# PicoMiteVGAUSBV1_1.net
KiCad netlist of a schematic drawn in EasyEDA Pro
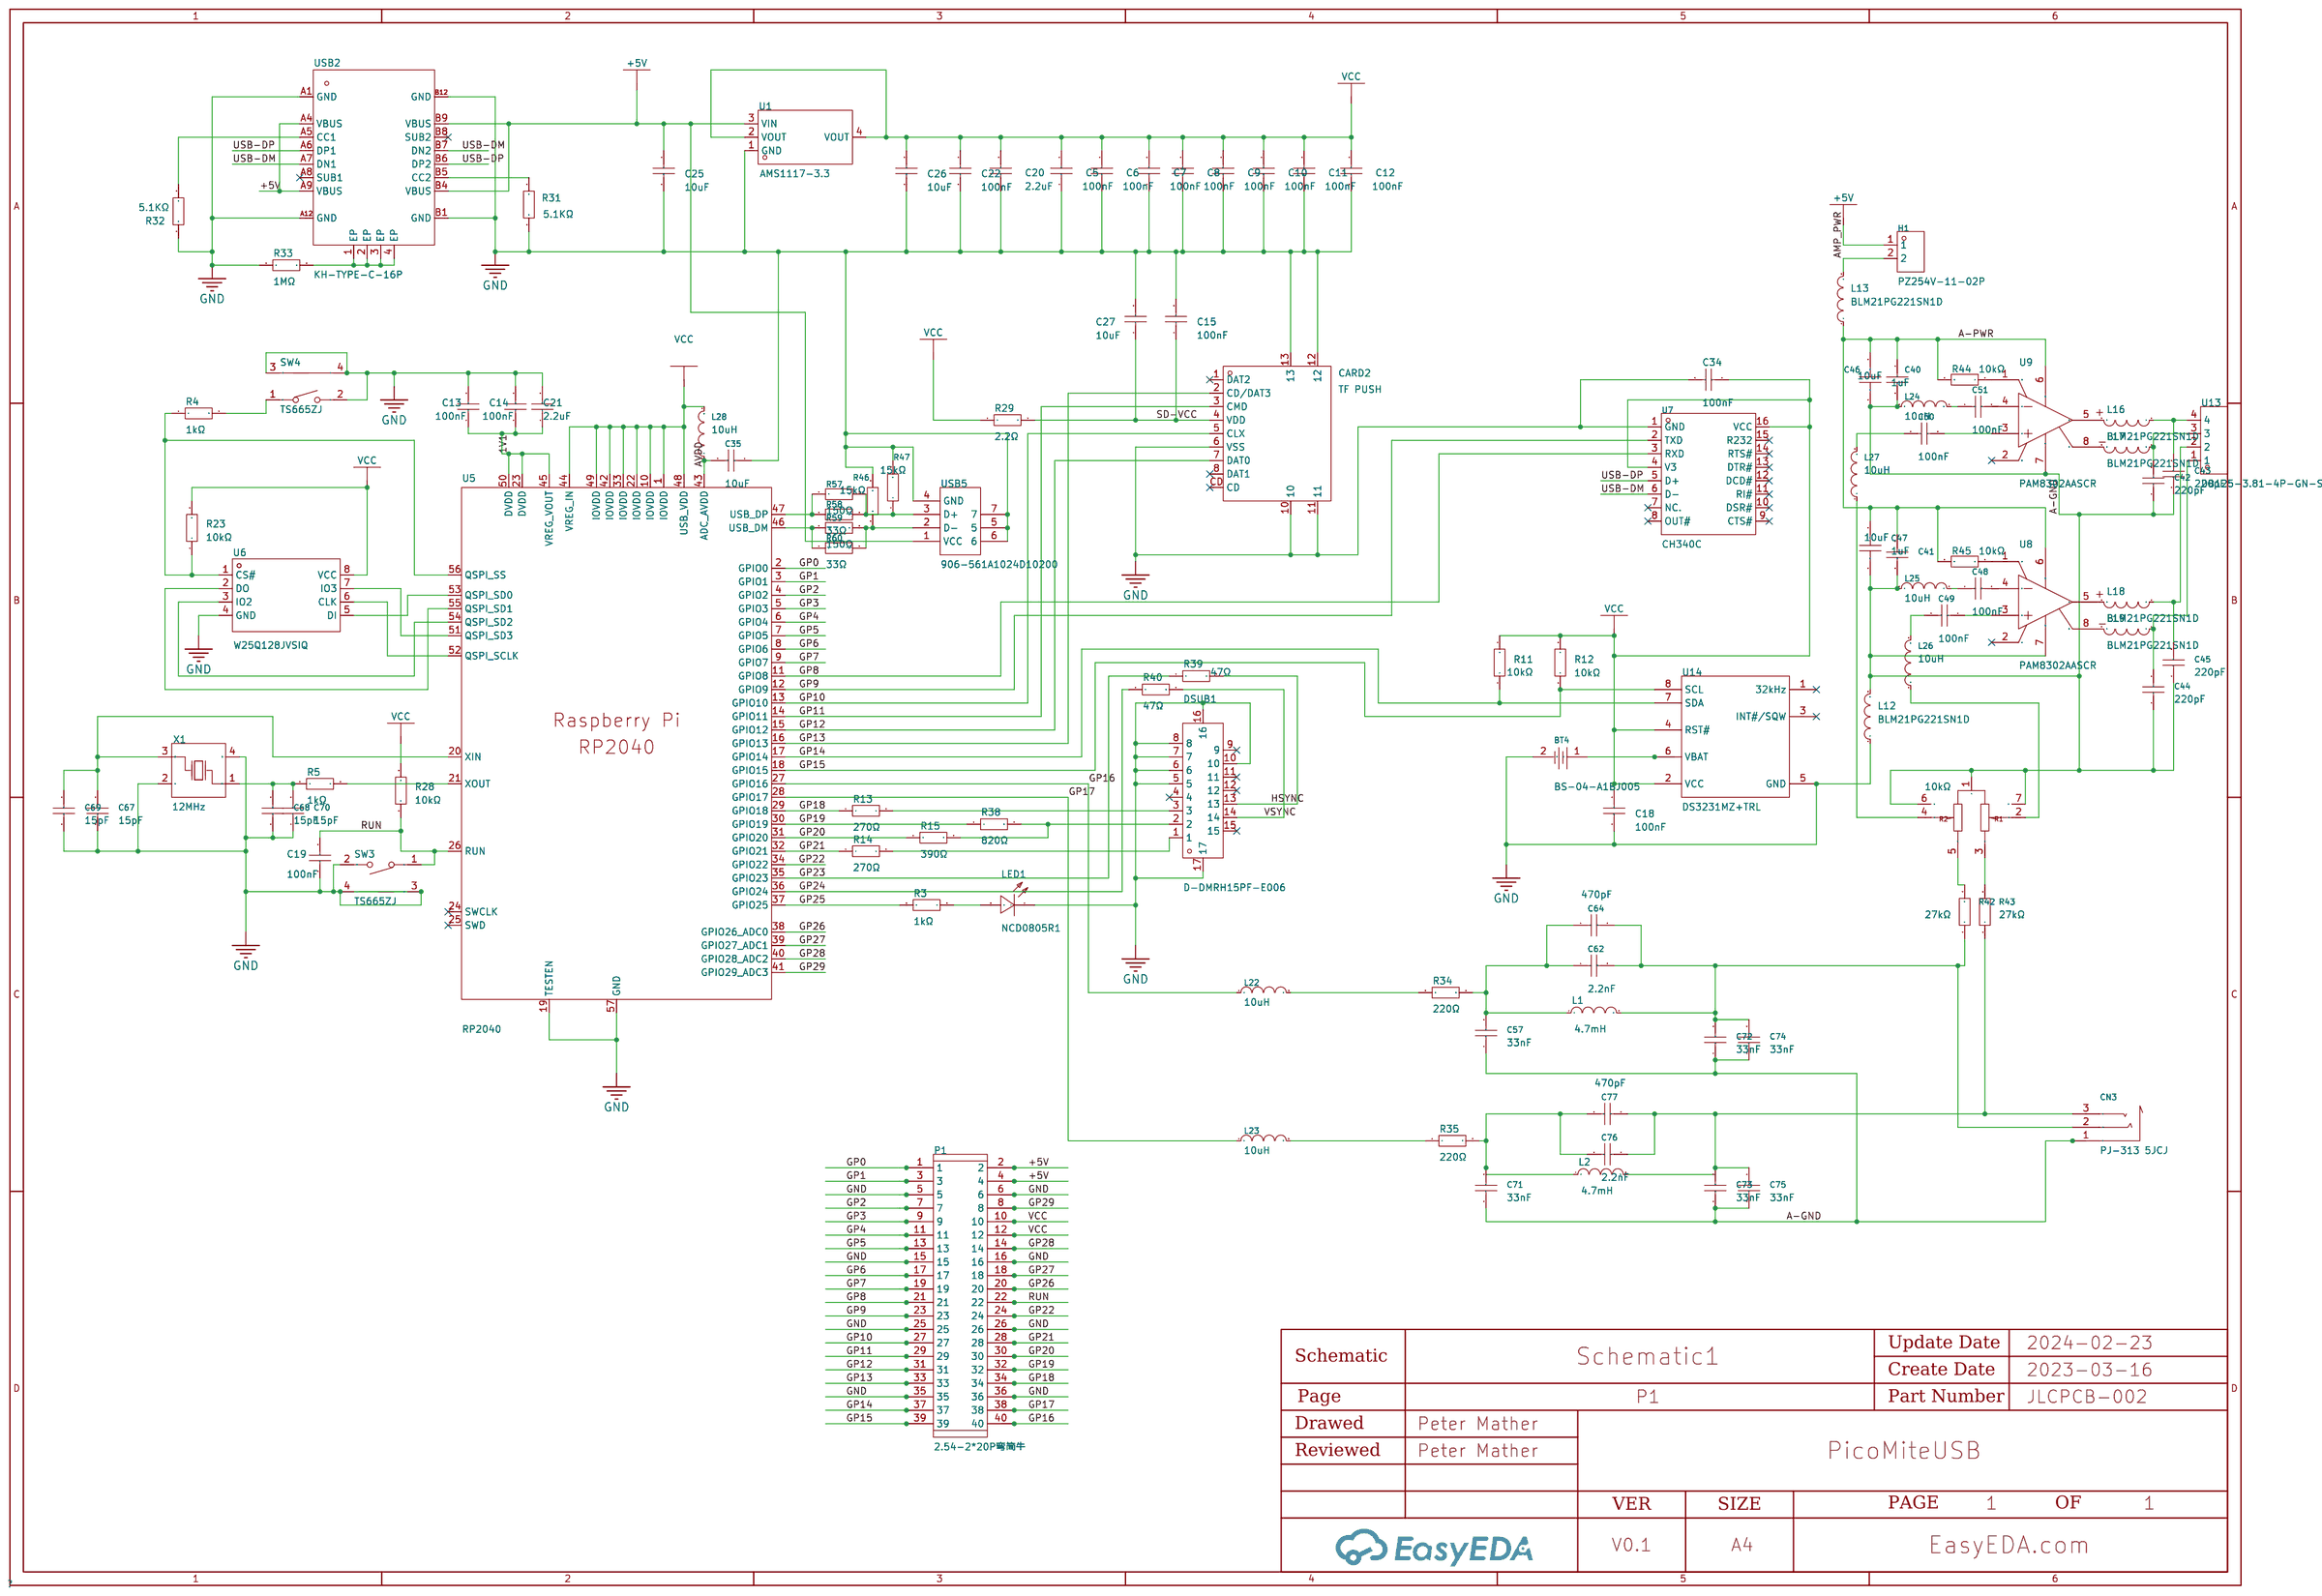
[diagram p0: schematic sheet]

(export (version "E")
  (design (tool "Eeschema 10.0.6"))
  (components
    (comp (ref "BT4")
      (value "BS-04-A1BJ005")
      (footprint "easyedapro:BAT-TH_BS-04-A1BJ004")
      (fields (field (name "Manufacturer") "MYOUNG(美阳)"))
      (libsource (lib "easyedapro") (part "BS-04-A1BJ005"))
    )
    (comp (ref "C5")
      (value "100nF")
      (footprint "easyedapro:C0603")
      (fields
        (field (name "Manufacturer Part") "CL05B104KO5NNNC")
        (field (name "Manufacturer") "SAMSUNG(三星)")
      )
      (libsource (lib "easyedapro") (part "CL10A225KO8NNNC"))
    )
    (comp (ref "C6")
      (value "100nF")
      (footprint "easyedapro:C0603")
      (fields
        (field (name "Manufacturer Part") "CL05B104KO5NNNC")
        (field (name "Manufacturer") "SAMSUNG(三星)")
      )
      (libsource (lib "easyedapro") (part "CL10A225KO8NNNC"))
    )
    (comp (ref "C7")
      (value "100nF")
      (footprint "easyedapro:C0603")
      (fields
        (field (name "Manufacturer Part") "CL05B104KO5NNNC")
        (field (name "Manufacturer") "SAMSUNG(三星)")
      )
      (libsource (lib "easyedapro") (part "CL10A225KO8NNNC"))
    )
    (comp (ref "C8")
      (value "100nF")
      (footprint "easyedapro:C0603")
      (fields
        (field (name "Manufacturer Part") "CL05B104KO5NNNC")
        (field (name "Manufacturer") "SAMSUNG(三星)")
      )
      (libsource (lib "easyedapro") (part "CL10A225KO8NNNC"))
    )
    (comp (ref "C9")
      (value "100nF")
      (footprint "easyedapro:C0603")
      (fields
        (field (name "Manufacturer Part") "CL05B104KO5NNNC")
        (field (name "Manufacturer") "SAMSUNG(三星)")
      )
      (libsource (lib "easyedapro") (part "CL10A225KO8NNNC"))
    )
    (comp (ref "C10")
      (value "100nF")
      (footprint "easyedapro:C0603")
      (fields
        (field (name "Manufacturer Part") "CL05B104KO5NNNC")
        (field (name "Manufacturer") "SAMSUNG(三星)")
      )
      (libsource (lib "easyedapro") (part "CL10A225KO8NNNC"))
    )
    (comp (ref "C11")
      (value "100nF")
      (footprint "easyedapro:C0603")
      (fields
        (field (name "Manufacturer Part") "CL05B104KO5NNNC")
        (field (name "Manufacturer") "SAMSUNG(三星)")
      )
      (libsource (lib "easyedapro") (part "CL10A225KO8NNNC"))
    )
    (comp (ref "C12")
      (value "100nF")
      (footprint "easyedapro:C0603")
      (fields
        (field (name "Manufacturer Part") "CL05B104KO5NNNC")
        (field (name "Manufacturer") "SAMSUNG(三星)")
      )
      (libsource (lib "easyedapro") (part "CL10A225KO8NNNC"))
    )
    (comp (ref "C13")
      (value "100nF")
      (footprint "easyedapro:C0603")
      (fields
        (field (name "Manufacturer Part") "CL05B104KO5NNNC")
        (field (name "Manufacturer") "SAMSUNG(三星)")
      )
      (libsource (lib "easyedapro") (part "CL10A225KO8NNNC"))
    )
    (comp (ref "C14")
      (value "100nF")
      (footprint "easyedapro:C0603")
      (fields
        (field (name "Manufacturer Part") "CL05B104KO5NNNC")
        (field (name "Manufacturer") "SAMSUNG(三星)")
      )
      (libsource (lib "easyedapro") (part "CL10A225KO8NNNC"))
    )
    (comp (ref "C15")
      (value "100nF")
      (footprint "easyedapro:C0603")
      (fields
        (field (name "Manufacturer Part") "CL05B104KO5NNNC")
        (field (name "Manufacturer") "SAMSUNG(三星)")
      )
      (libsource (lib "easyedapro") (part "CL10A225KO8NNNC"))
    )
    (comp (ref "C18")
      (value "100nF")
      (footprint "easyedapro:C0603")
      (fields
        (field (name "Manufacturer Part") "CL05B104KO5NNNC")
        (field (name "Manufacturer") "SAMSUNG(三星)")
      )
      (libsource (lib "easyedapro") (part "CL10A225KO8NNNC"))
    )
    (comp (ref "C19")
      (value "100nF")
      (footprint "easyedapro:C0603")
      (fields
        (field (name "Manufacturer Part") "CL05B104KO5NNNC")
        (field (name "Manufacturer") "SAMSUNG(三星)")
      )
      (libsource (lib "easyedapro") (part "CL10A225KO8NNNC"))
    )
    (comp (ref "C20")
      (value "2.2uF")
      (footprint "easyedapro:C0402_NEW")
      (fields
        (field (name "Manufacturer Part") "CL10A225KO8NNNC")
        (field (name "Manufacturer") "SAMSUNG(三星)")
      )
      (libsource (lib "easyedapro") (part "CL05B104KO5NNNC"))
    )
    (comp (ref "C21")
      (value "2.2uF")
      (footprint "easyedapro:C0402_NEW")
      (fields
        (field (name "Manufacturer Part") "CL10A225KO8NNNC")
        (field (name "Manufacturer") "SAMSUNG(三星)")
      )
      (libsource (lib "easyedapro") (part "CL05B104KO5NNNC"))
    )
    (comp (ref "C22")
      (value "100nF")
      (footprint "easyedapro:C0603")
      (fields
        (field (name "Manufacturer Part") "CL05B104KO5NNNC")
        (field (name "Manufacturer") "SAMSUNG(三星)")
      )
      (libsource (lib "easyedapro") (part "CL10A225KO8NNNC"))
    )
    (comp (ref "C25")
      (value "10uF")
      (footprint "easyedapro:C1206")
      (fields
        (field (name "Manufacturer Part") "CL31A106KBHNNNE")
        (field (name "Manufacturer") "SAMSUNG(三星)")
      )
      (libsource (lib "easyedapro") (part "CL31A106KBHNNNE"))
    )
    (comp (ref "C26")
      (value "10uF")
      (footprint "easyedapro:C1206")
      (fields
        (field (name "Manufacturer Part") "CL31A106KBHNNNE")
        (field (name "Manufacturer") "SAMSUNG(三星)")
      )
      (libsource (lib "easyedapro") (part "CL31A106KBHNNNE"))
    )
    (comp (ref "C27")
      (value "10uF")
      (footprint "easyedapro:C1206")
      (fields
        (field (name "Manufacturer Part") "CL31A106KBHNNNE")
        (field (name "Manufacturer") "SAMSUNG(三星)")
      )
      (libsource (lib "easyedapro") (part "CL31A106KBHNNNE"))
    )
    (comp (ref "C34")
      (value "100nF")
      (footprint "easyedapro:C0603")
      (fields
        (field (name "Manufacturer Part") "CL05B104KO5NNNC")
        (field (name "Manufacturer") "SAMSUNG(三星)")
      )
      (libsource (lib "easyedapro") (part "CL10A225KO8NNNC"))
    )
    (comp (ref "C35")
      (value "10uF")
      (footprint "easyedapro:C1206")
      (fields
        (field (name "Manufacturer Part") "CL31A106KBHNNNE")
        (field (name "Manufacturer") "SAMSUNG(三星)")
      )
      (libsource (lib "easyedapro") (part "CL31A106KBHNNNE"))
    )
    (comp (ref "C40")
      (value "10uF")
      (footprint "easyedapro:C1206")
      (fields
        (field (name "Manufacturer Part") "CL31A106KBHNNNE")
        (field (name "Manufacturer") "SAMSUNG(三星)")
      )
      (libsource (lib "easyedapro") (part "CL31A106KBHNNNE"))
    )
    (comp (ref "C41")
      (value "10uF")
      (footprint "easyedapro:C1206")
      (fields
        (field (name "Manufacturer Part") "CL31A106KBHNNNE")
        (field (name "Manufacturer") "SAMSUNG(三星)")
      )
      (libsource (lib "easyedapro") (part "CL31A106KBHNNNE"))
    )
    (comp (ref "C42")
      (value "220pF")
      (footprint "easyedapro:C0402")
      (fields (field (name "Manufacturer Part") "0402B221K500NT") (field (name "Manufacturer") "FH(风华)"))
      (libsource (lib "easyedapro") (part "0402B221K500NT"))
    )
    (comp (ref "C43")
      (value "220pF")
      (footprint "easyedapro:C0402")
      (fields (field (name "Manufacturer Part") "0402B221K500NT") (field (name "Manufacturer") "FH(风华)"))
      (libsource (lib "easyedapro") (part "0402B221K500NT"))
    )
    (comp (ref "C44")
      (value "220pF")
      (footprint "easyedapro:C0402")
      (fields (field (name "Manufacturer Part") "0402B221K500NT") (field (name "Manufacturer") "FH(风华)"))
      (libsource (lib "easyedapro") (part "0402B221K500NT"))
    )
    (comp (ref "C45")
      (value "220pF")
      (footprint "easyedapro:C0402")
      (fields (field (name "Manufacturer Part") "0402B221K500NT") (field (name "Manufacturer") "FH(风华)"))
      (libsource (lib "easyedapro") (part "0402B221K500NT"))
    )
    (comp (ref "C46")
      (value "1uF")
      (footprint "easyedapro:C1206")
      (fields
        (field (name "Manufacturer Part") "CL31B105KBHNNNE")
        (field (name "Manufacturer") "SAMSUNG(三星)")
      )
      (libsource (lib "easyedapro") (part "CL31B105KBHNNNE"))
    )
    (comp (ref "C47")
      (value "1uF")
      (footprint "easyedapro:C1206")
      (fields
        (field (name "Manufacturer Part") "CL31B105KBHNNNE")
        (field (name "Manufacturer") "SAMSUNG(三星)")
      )
      (libsource (lib "easyedapro") (part "CL31B105KBHNNNE"))
    )
    (comp (ref "C48")
      (value "100nF")
      (footprint "easyedapro:C0805")
      (fields
        (field (name "Manufacturer Part") "CC0805KRX7R9BB104")
        (field (name "Manufacturer") "YAGEO(国巨)")
      )
      (libsource (lib "easyedapro") (part "CC0805KRX7R9BB104"))
    )
    (comp (ref "C49")
      (value "100nF")
      (footprint "easyedapro:C0805")
      (fields
        (field (name "Manufacturer Part") "CC0805KRX7R9BB104")
        (field (name "Manufacturer") "YAGEO(国巨)")
      )
      (libsource (lib "easyedapro") (part "CC0805KRX7R9BB104"))
    )
    (comp (ref "C50")
      (value "100nF")
      (footprint "easyedapro:C0805")
      (fields
        (field (name "Manufacturer Part") "CC0805KRX7R9BB104")
        (field (name "Manufacturer") "YAGEO(国巨)")
      )
      (libsource (lib "easyedapro") (part "CC0805KRX7R9BB104"))
    )
    (comp (ref "C51")
      (value "100nF")
      (footprint "easyedapro:C0805")
      (fields
        (field (name "Manufacturer Part") "CC0805KRX7R9BB104")
        (field (name "Manufacturer") "YAGEO(国巨)")
      )
      (libsource (lib "easyedapro") (part "CC0805KRX7R9BB104"))
    )
    (comp (ref "C57")
      (value "33nF")
      (footprint "easyedapro:C0805")
      (fields (field (name "Manufacturer Part") "0805B333K500NT") (field (name "Manufacturer") "FH(风华)"))
      (libsource (lib "easyedapro") (part "0805B333K500NT"))
    )
    (comp (ref "C62")
      (value "2.2nF")
      (footprint "easyedapro:C0805")
      (fields
        (field (name "Manufacturer Part") "CL21C222JBFNNNE")
        (field (name "Manufacturer") "SAMSUNG(三星)")
      )
      (libsource (lib "easyedapro") (part "CL21C222JBFNNNE"))
    )
    (comp (ref "C64")
      (value "470pF")
      (footprint "easyedapro:C0603")
      (fields (field (name "Manufacturer Part") "0603B471K500NT") (field (name "Manufacturer") "FH(风华)"))
      (libsource (lib "easyedapro") (part "0603B471K500NT"))
    )
    (comp (ref "C67")
      (value "15pF")
      (footprint "easyedapro:C0402")
      (fields (field (name "Manufacturer Part") "0402CG150J500NT") (field (name "Manufacturer") "FH(风华)"))
      (libsource (lib "easyedapro") (part "0402CG150J500NT"))
    )
    (comp (ref "C68")
      (value "15pF")
      (footprint "easyedapro:C0402")
      (fields (field (name "Manufacturer Part") "0402CG150J500NT") (field (name "Manufacturer") "FH(风华)"))
      (libsource (lib "easyedapro") (part "0402CG150J500NT"))
    )
    (comp (ref "C69")
      (value "15pF")
      (footprint "easyedapro:C0402")
      (fields (field (name "Manufacturer Part") "0402CG150J500NT") (field (name "Manufacturer") "FH(风华)"))
      (libsource (lib "easyedapro") (part "0402CG150J500NT"))
    )
    (comp (ref "C70")
      (value "15pF")
      (footprint "easyedapro:C0402")
      (fields (field (name "Manufacturer Part") "0402CG150J500NT") (field (name "Manufacturer") "FH(风华)"))
      (libsource (lib "easyedapro") (part "0402CG150J500NT"))
    )
    (comp (ref "C71")
      (value "33nF")
      (footprint "easyedapro:C0805")
      (fields (field (name "Manufacturer Part") "0805B333K500NT") (field (name "Manufacturer") "FH(风华)"))
      (libsource (lib "easyedapro") (part "0805B333K500NT"))
    )
    (comp (ref "C72")
      (value "33nF")
      (footprint "easyedapro:C0805")
      (fields (field (name "Manufacturer Part") "0805B333K500NT") (field (name "Manufacturer") "FH(风华)"))
      (libsource (lib "easyedapro") (part "0805B333K500NT"))
    )
    (comp (ref "C73")
      (value "33nF")
      (footprint "easyedapro:C0805")
      (fields (field (name "Manufacturer Part") "0805B333K500NT") (field (name "Manufacturer") "FH(风华)"))
      (libsource (lib "easyedapro") (part "0805B333K500NT"))
    )
    (comp (ref "C74")
      (value "33nF")
      (footprint "easyedapro:C0805")
      (fields (field (name "Manufacturer Part") "0805B333K500NT") (field (name "Manufacturer") "FH(风华)"))
      (libsource (lib "easyedapro") (part "0805B333K500NT"))
    )
    (comp (ref "C75")
      (value "33nF")
      (footprint "easyedapro:C0805")
      (fields (field (name "Manufacturer Part") "0805B333K500NT") (field (name "Manufacturer") "FH(风华)"))
      (libsource (lib "easyedapro") (part "0805B333K500NT"))
    )
    (comp (ref "C76")
      (value "2.2nF")
      (footprint "easyedapro:C0805")
      (fields
        (field (name "Manufacturer Part") "CL21C222JBFNNNE")
        (field (name "Manufacturer") "SAMSUNG(三星)")
      )
      (libsource (lib "easyedapro") (part "CL21C222JBFNNNE"))
    )
    (comp (ref "C77")
      (value "470pF")
      (footprint "easyedapro:C0603")
      (fields (field (name "Manufacturer Part") "0603B471K500NT") (field (name "Manufacturer") "FH(风华)"))
      (libsource (lib "easyedapro") (part "0603B471K500NT"))
    )
    (comp (ref "CARD2")
      (value "TF PUSH")
      (footprint "easyedapro:TF-SMD_TF-PUSH")
      (fields (field (name "Manufacturer") "SHOU HAN(首韩)"))
      (libsource (lib "easyedapro") (part "TF PUSH"))
    )
    (comp (ref "CN3")
      (value "PJ-313 5JCJ")
      (footprint "easyedapro:AUDIO-TH_PJ-313_5JCJ")
      (fields (field (name "Manufacturer") "SHOU HAN(首韩)"))
      (libsource (lib "easyedapro") (part "PJ-313 5JCJ"))
    )
    (comp (ref "DSUB1")
      (value "D-DMRH15PF-E006")
      (footprint "easyedapro:DSUB-TH_15P-P2.29-H-F_DDMRH15PFE006")
      (fields (field (name "Manufacturer") "Ckmtw(灿科盟)"))
      (libsource (lib "easyedapro") (part "DDMRH15PFE006"))
    )
    (comp (ref "H1")
      (value "PZ254V-11-02P")
      (footprint "easyedapro:HDR-TH_2P-P2.54-V-M")
      (fields (field (name "Manufacturer") "XFCN(兴飞)"))
      (libsource (lib "easyedapro") (part "PZ254V-11-02P"))
    )
    (comp (ref "L1")
      (value "4.7mH")
      (footprint "easyedapro:IND-SMD_L6.0-W6.0")
      (fields (field (name "Manufacturer Part") "YNR6045-472M") (field (name "Manufacturer") "YJYCOIN(益嘉源)"))
      (libsource (lib "easyedapro") (part "YNR6045-472M"))
    )
    (comp (ref "L2")
      (value "4.7mH")
      (footprint "easyedapro:IND-SMD_L6.0-W6.0")
      (fields (field (name "Manufacturer Part") "YNR6045-472M") (field (name "Manufacturer") "YJYCOIN(益嘉源)"))
      (libsource (lib "easyedapro") (part "YNR6045-472M"))
    )
    (comp (ref "L12")
      (value "BLM21PG221SN1D")
      (footprint "easyedapro:L0805")
      (fields (field (name "Manufacturer") "muRata(村田)"))
      (libsource (lib "easyedapro") (part "BLM21PG221SN1D"))
    )
    (comp (ref "L13")
      (value "BLM21PG221SN1D")
      (footprint "easyedapro:L0805")
      (fields (field (name "Manufacturer") "muRata(村田)"))
      (libsource (lib "easyedapro") (part "BLM21PG221SN1D"))
    )
    (comp (ref "L16")
      (value "BLM21PG221SN1D")
      (footprint "easyedapro:L0805")
      (fields (field (name "Manufacturer") "muRata(村田)"))
      (libsource (lib "easyedapro") (part "BLM21PG221SN1D"))
    )
    (comp (ref "L17")
      (value "BLM21PG221SN1D")
      (footprint "easyedapro:L0805")
      (fields (field (name "Manufacturer") "muRata(村田)"))
      (libsource (lib "easyedapro") (part "BLM21PG221SN1D"))
    )
    (comp (ref "L18")
      (value "BLM21PG221SN1D")
      (footprint "easyedapro:L0805")
      (fields (field (name "Manufacturer") "muRata(村田)"))
      (libsource (lib "easyedapro") (part "BLM21PG221SN1D"))
    )
    (comp (ref "L19")
      (value "BLM21PG221SN1D")
      (footprint "easyedapro:L0805")
      (fields (field (name "Manufacturer") "muRata(村田)"))
      (libsource (lib "easyedapro") (part "BLM21PG221SN1D"))
    )
    (comp (ref "L22")
      (value "10uH")
      (footprint "easyedapro:L0805")
      (fields
        (field (name "Manufacturer Part") "SDFL2012S100KTF")
        (field (name "Manufacturer") "Sunlord(顺络)")
      )
      (libsource (lib "easyedapro") (part "SDFL2012S100KTF"))
    )
    (comp (ref "L23")
      (value "10uH")
      (footprint "easyedapro:L0805")
      (fields
        (field (name "Manufacturer Part") "SDFL2012S100KTF")
        (field (name "Manufacturer") "Sunlord(顺络)")
      )
      (libsource (lib "easyedapro") (part "SDFL2012S100KTF"))
    )
    (comp (ref "L24")
      (value "10uH")
      (footprint "easyedapro:L0805")
      (fields
        (field (name "Manufacturer Part") "SDFL2012S100KTF")
        (field (name "Manufacturer") "Sunlord(顺络)")
      )
      (libsource (lib "easyedapro") (part "SDFL2012S100KTF"))
    )
    (comp (ref "L25")
      (value "10uH")
      (footprint "easyedapro:L0805")
      (fields
        (field (name "Manufacturer Part") "SDFL2012S100KTF")
        (field (name "Manufacturer") "Sunlord(顺络)")
      )
      (libsource (lib "easyedapro") (part "SDFL2012S100KTF"))
    )
    (comp (ref "L26")
      (value "10uH")
      (footprint "easyedapro:L0805")
      (fields
        (field (name "Manufacturer Part") "SDFL2012S100KTF")
        (field (name "Manufacturer") "Sunlord(顺络)")
      )
      (libsource (lib "easyedapro") (part "SDFL2012S100KTF"))
    )
    (comp (ref "L27")
      (value "10uH")
      (footprint "easyedapro:L0805")
      (fields
        (field (name "Manufacturer Part") "SDFL2012S100KTF")
        (field (name "Manufacturer") "Sunlord(顺络)")
      )
      (libsource (lib "easyedapro") (part "SDFL2012S100KTF"))
    )
    (comp (ref "L28")
      (value "10uH")
      (footprint "easyedapro:L0805")
      (fields
        (field (name "Manufacturer Part") "SDFL2012S100KTF")
        (field (name "Manufacturer") "Sunlord(顺络)")
      )
      (libsource (lib "easyedapro") (part "SDFL2012S100KTF"))
    )
    (comp (ref "LED1")
      (value "NCD0805R1")
      (footprint "easyedapro:LED0805-RD")
      (description "Emitted Color:红灯")
      (fields (field (name "Manufacturer") "国星光电"))
      (libsource (lib "easyedapro") (part "FC-2012HRK-620D"))
    )
    (comp (ref "P1")
      (value "2.54-2*20P弯简牛")
      (footprint "easyedapro:IDC-TH_40P-P2.54-C9145")
      (fields (field (name "Manufacturer") "BOOMELE(博穆精密)"))
      (libsource (lib "easyedapro") (part "IDC Box 2X20 2.54MM"))
    )
    (comp (ref "R3")
      (value "1kΩ")
      (footprint "easyedapro:R0603")
      (fields
        (field (name "Manufacturer Part") "0603WAF1001T5E")
        (field (name "Manufacturer") "UNI-ROYAL(厚声)")
      )
      (libsource (lib "easyedapro") (part "0603WAF1001T5E"))
    )
    (comp (ref "R4")
      (value "1kΩ")
      (footprint "easyedapro:R0603")
      (fields
        (field (name "Manufacturer Part") "0603WAF1001T5E")
        (field (name "Manufacturer") "UNI-ROYAL(厚声)")
      )
      (libsource (lib "easyedapro") (part "0603WAF1001T5E"))
    )
    (comp (ref "R5")
      (value "1kΩ")
      (footprint "easyedapro:R0603")
      (fields
        (field (name "Manufacturer Part") "0603WAF1001T5E")
        (field (name "Manufacturer") "UNI-ROYAL(厚声)")
      )
      (libsource (lib "easyedapro") (part "0603WAF1001T5E"))
    )
    (comp (ref "R11")
      (value "10kΩ")
      (footprint "easyedapro:R0805")
      (fields
        (field (name "Manufacturer Part") "0805W8F1002T5E")
        (field (name "Manufacturer") "UNI-ROYAL(厚声)")
      )
      (libsource (lib "easyedapro") (part "0805W8F1002T5E"))
    )
    (comp (ref "R12")
      (value "10kΩ")
      (footprint "easyedapro:R0805")
      (fields
        (field (name "Manufacturer Part") "0805W8F1002T5E")
        (field (name "Manufacturer") "UNI-ROYAL(厚声)")
      )
      (libsource (lib "easyedapro") (part "0805W8F1002T5E"))
    )
    (comp (ref "R13")
      (value "270Ω")
      (footprint "easyedapro:R0603")
      (fields
        (field (name "Manufacturer Part") "0603WAF2700T5E")
        (field (name "Manufacturer") "UNI-ROYAL(厚声)")
      )
      (libsource (lib "easyedapro") (part "0603WAF2700T5E"))
    )
    (comp (ref "R14")
      (value "270Ω")
      (footprint "easyedapro:R0603")
      (fields
        (field (name "Manufacturer Part") "0603WAF2700T5E")
        (field (name "Manufacturer") "UNI-ROYAL(厚声)")
      )
      (libsource (lib "easyedapro") (part "0603WAF2700T5E"))
    )
    (comp (ref "R15")
      (value "390Ω")
      (footprint "easyedapro:R0603")
      (fields
        (field (name "Manufacturer Part") "0603WAF3900T5E")
        (field (name "Manufacturer") "UNI-ROYAL(厚声)")
      )
      (libsource (lib "easyedapro") (part "0603WAF3900T5E"))
    )
    (comp (ref "R23")
      (value "10kΩ")
      (footprint "easyedapro:R0402")
      (fields
        (field (name "Manufacturer Part") "0402WGF1002TCE")
        (field (name "Manufacturer") "UNI-ROYAL(厚声)")
      )
      (libsource (lib "easyedapro") (part "0402WGF1002TCE"))
    )
    (comp (ref "R28")
      (value "10kΩ")
      (footprint "easyedapro:R0402")
      (fields
        (field (name "Manufacturer Part") "0402WGF1002TCE")
        (field (name "Manufacturer") "UNI-ROYAL(厚声)")
      )
      (libsource (lib "easyedapro") (part "0402WGF1002TCE"))
    )
    (comp (ref "R29")
      (value "2.2Ω")
      (footprint "easyedapro:R0805")
      (fields (field (name "Manufacturer") "UNI-ROYAL(厚声)"))
      (libsource (lib "easyedapro") (part "0805W8F220KT5E"))
    )
    (comp (ref "R31")
      (value "5.1kΩ")
      (footprint "easyedapro:R0603")
      (fields
        (field (name "Manufacturer Part") "5.1KΩ")
        (field (name "Manufacturer") "UNI-ROYAL(厚声)")
        (field (name "Tolerance") "±1%")
      )
      (libsource (lib "easyedapro") (part "0603WAF5101T5E"))
    )
    (comp (ref "R32")
      (value "5.1kΩ")
      (footprint "easyedapro:R0603")
      (fields
        (field (name "Manufacturer Part") "5.1KΩ")
        (field (name "Manufacturer") "UNI-ROYAL(厚声)")
        (field (name "Tolerance") "±1%")
      )
      (libsource (lib "easyedapro") (part "0603WAF5101T5E"))
    )
    (comp (ref "R33")
      (value "1MΩ")
      (footprint "easyedapro:R0603")
      (fields
        (field (name "Manufacturer Part") "0402WGF1004TCE")
        (field (name "Manufacturer") "UNI-ROYAL(厚声)")
        (field (name "Tolerance") "±1%")
      )
      (libsource (lib "easyedapro") (part "0603WAF1004T5E"))
    )
    (comp (ref "R34")
      (value "220Ω")
      (footprint "easyedapro:R0603")
      (fields
        (field (name "Manufacturer Part") "0603WAF2200T5E")
        (field (name "Manufacturer") "UNI-ROYAL(厚声)")
      )
      (libsource (lib "easyedapro") (part "0603WAF2200T5E"))
    )
    (comp (ref "R35")
      (value "220Ω")
      (footprint "easyedapro:R0603")
      (fields
        (field (name "Manufacturer Part") "0603WAF2200T5E")
        (field (name "Manufacturer") "UNI-ROYAL(厚声)")
      )
      (libsource (lib "easyedapro") (part "0603WAF2200T5E"))
    )
    (comp (ref "R38")
      (value "820Ω")
      (footprint "easyedapro:R0603")
      (fields
        (field (name "Manufacturer Part") "0603WAF8200T5E")
        (field (name "Manufacturer") "UNI-ROYAL(厚声)")
      )
      (libsource (lib "easyedapro") (part "0603WAF8200T5E"))
    )
    (comp (ref "R39")
      (value "47Ω")
      (footprint "easyedapro:R0805")
      (fields
        (field (name "Manufacturer Part") "0805W8F470JT5E")
        (field (name "Manufacturer") "UNI-ROYAL(厚声)")
      )
      (libsource (lib "easyedapro") (part "0805W8F470JT5E"))
    )
    (comp (ref "R40")
      (value "47Ω")
      (footprint "easyedapro:R0805")
      (fields
        (field (name "Manufacturer Part") "0805W8F470JT5E")
        (field (name "Manufacturer") "UNI-ROYAL(厚声)")
      )
      (libsource (lib "easyedapro") (part "0805W8F470JT5E"))
    )
    (comp (ref "R42")
      (value "27kΩ")
      (footprint "easyedapro:R0805")
      (fields
        (field (name "Manufacturer Part") "0805W8F2702T5E")
        (field (name "Manufacturer") "UNI-ROYAL(厚声)")
      )
      (libsource (lib "easyedapro") (part "0805W8F2702T5E"))
    )
    (comp (ref "R43")
      (value "27kΩ")
      (footprint "easyedapro:R0805")
      (fields
        (field (name "Manufacturer Part") "0805W8F2702T5E")
        (field (name "Manufacturer") "UNI-ROYAL(厚声)")
      )
      (libsource (lib "easyedapro") (part "0805W8F2702T5E"))
    )
    (comp (ref "R44")
      (value "10kΩ")
      (footprint "easyedapro:R0805")
      (fields
        (field (name "Manufacturer Part") "0805W8F1002T5E")
        (field (name "Manufacturer") "UNI-ROYAL(厚声)")
      )
      (libsource (lib "easyedapro") (part "0805W8F1002T5E"))
    )
    (comp (ref "R45")
      (value "10kΩ")
      (footprint "easyedapro:R0805")
      (fields
        (field (name "Manufacturer Part") "0805W8F1002T5E")
        (field (name "Manufacturer") "UNI-ROYAL(厚声)")
      )
      (libsource (lib "easyedapro") (part "0805W8F1002T5E"))
    )
    (comp (ref "R46")
      (value "15kΩ")
      (footprint "easyedapro:R0805")
      (fields
        (field (name "Manufacturer Part") "0805W8F1502T5E")
        (field (name "Manufacturer") "UNI-ROYAL(厚声)")
      )
      (libsource (lib "easyedapro") (part "0805W8F1502T5E"))
    )
    (comp (ref "R47")
      (value "15kΩ")
      (footprint "easyedapro:R0805")
      (fields
        (field (name "Manufacturer Part") "0805W8F1502T5E")
        (field (name "Manufacturer") "UNI-ROYAL(厚声)")
      )
      (libsource (lib "easyedapro") (part "0805W8F1502T5E"))
    )
    (comp (ref "R57")
      (value "150Ω")
      (footprint "easyedapro:R0603")
      (fields
        (field (name "Manufacturer Part") "0603WAF1500T5E")
        (field (name "Manufacturer") "UNI-ROYAL(厚声)")
      )
      (libsource (lib "easyedapro") (part "0603WAF1500T5E"))
    )
    (comp (ref "R58")
      (value "33Ω")
      (footprint "easyedapro:R0805")
      (fields
        (field (name "Manufacturer Part") "0805W8F330JT5E")
        (field (name "Manufacturer") "UNI-ROYAL(厚声)")
      )
      (libsource (lib "easyedapro") (part "0805W8F330JT5E"))
    )
    (comp (ref "R59")
      (value "150Ω")
      (footprint "easyedapro:R0603")
      (fields
        (field (name "Manufacturer Part") "0603WAF1500T5E")
        (field (name "Manufacturer") "UNI-ROYAL(厚声)")
      )
      (libsource (lib "easyedapro") (part "0603WAF1500T5E"))
    )
    (comp (ref "R60")
      (value "33Ω")
      (footprint "easyedapro:R0805")
      (fields
        (field (name "Manufacturer Part") "0805W8F330JT5E")
        (field (name "Manufacturer") "UNI-ROYAL(厚声)")
      )
      (libsource (lib "easyedapro") (part "0805W8F330JT5E"))
    )
    (comp (ref "SW3")
      (value "TS665ZJ")
      (footprint "easyedapro:SW-TH_TS665ZJ")
      (fields (field (name "Manufacturer") "SHOU HAN(首韩)"))
      (libsource (lib "easyedapro") (part "TS665ZJ"))
    )
    (comp (ref "SW4")
      (value "TS665ZJ")
      (footprint "easyedapro:SW-TH_TS665ZJ")
      (fields (field (name "Manufacturer") "SHOU HAN(首韩)"))
      (libsource (lib "easyedapro") (part "TS665ZJ"))
    )
    (comp (ref "U1")
      (value "AMS1117-3.3")
      (footprint "easyedapro:SOT-223-3_L6.5-W3.4-P2.30-LS7.0-BR")
      (fields (field (name "Manufacturer") "AMS"))
      (libsource (lib "easyedapro") (part "AMS1117-3.3"))
    )
    (comp (ref "U5")
      (value "RP2040")
      (footprint "easyedapro:LQFN-56_L7.0-W7.0-P0.4-EP")
      (fields (field (name "Manufacturer") "Raspberry Pi(树莓派)"))
      (libsource (lib "easyedapro") (part "RP2040"))
    )
    (comp (ref "U6")
      (value "W25Q128JVSIQ")
      (footprint "easyedapro:SOIC-8_L5.3-W5.3-P1.27-LS8.0-BL")
      (fields (field (name "Manufacturer") "WINBOND(华邦)"))
      (libsource (lib "easyedapro") (part "W25Q128JVSIQTR"))
    )
    (comp (ref "U7")
      (value "CH340C")
      (footprint "easyedapro:SOP-16_L10.0-W3.9-P1.27-LS6.0-BL")
      (fields (field (name "Manufacturer") "WCH(南京沁恒)"))
      (libsource (lib "easyedapro") (part "CH340C"))
    )
    (comp (ref "U8")
      (value "PAM8302AASCR")
      (footprint "easyedapro:MSOP-8_L3.0-W3.0-P0.65-LS5.0-BL")
      (fields (field (name "Manufacturer") "DIODES(美台)"))
      (libsource (lib "easyedapro") (part "PAM8302AASCR"))
    )
    (comp (ref "U9")
      (value "PAM8302AASCR")
      (footprint "easyedapro:MSOP-8_L3.0-W3.0-P0.65-LS5.0-BL")
      (fields (field (name "Manufacturer") "DIODES(美台)"))
      (libsource (lib "easyedapro") (part "PAM8302AASCR"))
    )
    (comp (ref "U13")
      (value "DB125-3.81-4P-GN-S")
      (footprint "easyedapro:CONN-TH_DB125-3.81-4P")
      (fields (field (name "Manufacturer") "DORABO(地博电气)"))
      (libsource (lib "easyedapro") (part "DB125-3.81-4P"))
    )
    (comp (ref "U14")
      (value "DS3231MZ+TRL")
      (footprint "easyedapro:SOIC-8_L4.9-W3.9-P1.27-LS6.0-BL")
      (fields (field (name "Manufacturer") "MAXIM(美信)"))
      (libsource (lib "easyedapro") (part "DS3231MZ+"))
    )
    (comp (ref "USB2")
      (value "KH-TYPE-C-16P")
      (footprint "easyedapro:USB-C-SMD_KH-TYPE-C-16P")
      (fields (field (name "Manufacturer") "kinghelm(金航标)"))
      (libsource (lib "easyedapro") (part "KH-TYPE-C-16P"))
    )
    (comp (ref "USB5")
      (value "906-561A1024D10200")
      (footprint "easyedapro:USB-A-TH_C39450")
      (fields (field (name "Manufacturer") "精拓金"))
      (libsource (lib "easyedapro") (part "USB-AF-13.1X10.4-H5.1"))
    )
    (comp (ref "VR1")
      (value "10kΩ")
      (footprint "easyedapro:RES-TH_RK10J12E002L")
      (description "Resistance: Tolerance:±30% Tolerance:±30%")
      (fields
        (field (name "Manufacturer Part") "RK10J12E002L")
        (field (name "Manufacturer") "ALPSALPINE(阿尔卑斯阿尔派)")
      )
      (libsource (lib "easyedapro") (part "RK10J12E002L"))
    )
    (comp (ref "X1")
      (value "12MHz")
      (footprint "easyedapro:OSC-SMD_4P-L3.2-W2.5-BL")
      (fields (field (name "Manufacturer Part") "X322512MSB4SI") (field (name "Manufacturer") "YXC(扬兴晶振)"))
      (libsource (lib "easyedapro") (part "X322512MSB4SI"))
    )
  )
  (nets
    (net (code "1") (name "+5V") (class "Default")
      (node (ref "C25") (pin "2") (pinfunction "2_2") (pintype "input"))
      (node (ref "H1") (pin "1") (pinfunction "1_1") (pintype "input"))
      (node (ref "P1") (pin "2") (pinfunction "2_2") (pintype "input"))
      (node (ref "P1") (pin "4") (pinfunction "4_4") (pintype "input"))
      (node (ref "U1") (pin "3") (pinfunction "VIN_3") (pintype "input"))
      (node (ref "USB2") (pin "A4") (pinfunction "VBUS_A4") (pintype "input"))
      (node (ref "USB2") (pin "A9") (pinfunction "VBUS_A9") (pintype "input"))
      (node (ref "USB2") (pin "B4") (pinfunction "VBUS_B4") (pintype "input"))
      (node (ref "USB2") (pin "B9") (pinfunction "VBUS_B9") (pintype "input"))
      (node (ref "USB5") (pin "1") (pinfunction "VCC_1") (pintype "unspecified"))
    )
    (net (code "2") (name "/1V1") (class "Default")
      (node (ref "C13") (pin "1") (pinfunction "1_1") (pintype "input"))
      (node (ref "C14") (pin "1") (pinfunction "1_1") (pintype "input"))
      (node (ref "C21") (pin "1") (pinfunction "1_1") (pintype "input"))
      (node (ref "U5") (pin "23") (pinfunction "DVDD_23") (pintype "bidirectional"))
      (node (ref "U5") (pin "45") (pinfunction "VREG_VOUT_45") (pintype "bidirectional"))
      (node (ref "U5") (pin "50") (pinfunction "DVDD_50") (pintype "bidirectional"))
    )
    (net (code "3") (name "/A-GND") (class "Default")
      (node (ref "C40") (pin "2") (pinfunction "2_2") (pintype "input"))
      (node (ref "C41") (pin "2") (pinfunction "2_2") (pintype "input"))
      (node (ref "C42") (pin "1") (pinfunction "1_1") (pintype "input"))
      (node (ref "C43") (pin "1") (pinfunction "1_1") (pintype "input"))
      (node (ref "C44") (pin "1") (pinfunction "1_1") (pintype "input"))
      (node (ref "C45") (pin "1") (pinfunction "1_1") (pintype "input"))
      (node (ref "C46") (pin "1") (pinfunction "1_1") (pintype "input"))
      (node (ref "C47") (pin "1") (pinfunction "1_1") (pintype "input"))
      (node (ref "C57") (pin "1") (pinfunction "1_1") (pintype "input"))
      (node (ref "C71") (pin "1") (pinfunction "1_1") (pintype "input"))
      (node (ref "C72") (pin "1") (pinfunction "1_1") (pintype "input"))
      (node (ref "C73") (pin "1") (pinfunction "1_1") (pintype "input"))
      (node (ref "C74") (pin "1") (pinfunction "1_1") (pintype "input"))
      (node (ref "C75") (pin "1") (pinfunction "1_1") (pintype "input"))
      (node (ref "CN3") (pin "1") (pinfunction "1_1") (pintype "input"))
      (node (ref "L12") (pin "2") (pinfunction "2_2") (pintype "input"))
      (node (ref "L24") (pin "1") (pinfunction "1_1") (pintype "input"))
      (node (ref "L25") (pin "1") (pinfunction "1_1") (pintype "input"))
      (node (ref "U8") (pin "7") (pinfunction "GND_7") (pintype "input"))
      (node (ref "U9") (pin "7") (pinfunction "GND_7") (pintype "input"))
      (node (ref "VR1") (pin "1") (pinfunction "1_1") (pintype "input"))
      (node (ref "VR1") (pin "6") (pinfunction "EH_6") (pintype "input"))
      (node (ref "VR1") (pin "7") (pinfunction "EH_7") (pintype "input"))
    )
    (net (code "4") (name "/A-PWR") (class "Default")
      (node (ref "C40") (pin "1") (pinfunction "1_1") (pintype "input"))
      (node (ref "C41") (pin "1") (pinfunction "1_1") (pintype "input"))
      (node (ref "C46") (pin "2") (pinfunction "2_2") (pintype "input"))
      (node (ref "C47") (pin "2") (pinfunction "2_2") (pintype "input"))
      (node (ref "L13") (pin "1") (pinfunction "1_1") (pintype "input"))
      (node (ref "R44") (pin "2") (pinfunction "2_2") (pintype "input"))
      (node (ref "R45") (pin "2") (pinfunction "2_2") (pintype "input"))
      (node (ref "U8") (pin "6") (pinfunction "VDD_6") (pintype "input"))
      (node (ref "U9") (pin "6") (pinfunction "VDD_6") (pintype "input"))
    )
    (net (code "5") (name "/AMP_PWR") (class "Default")
      (node (ref "H1") (pin "2") (pinfunction "2_2") (pintype "input"))
      (node (ref "L13") (pin "2") (pinfunction "2_2") (pintype "input"))
    )
    (net (code "6") (name "/AVDD") (class "Default")
      (node (ref "C35") (pin "2") (pinfunction "2_2") (pintype "input"))
      (node (ref "L28") (pin "1") (pinfunction "1_1") (pintype "input"))
      (node (ref "U5") (pin "43") (pinfunction "ADC_AVDD_43") (pintype "bidirectional"))
    )
    (net (code "7") (name "/GP0") (class "Default")
      (node (ref "P1") (pin "1") (pinfunction "1_1") (pintype "input"))
      (node (ref "U5") (pin "2") (pinfunction "GPIO0_2") (pintype "bidirectional"))
    )
    (net (code "8") (name "/GP1") (class "Default")
      (node (ref "P1") (pin "3") (pinfunction "3_3") (pintype "input"))
      (node (ref "U5") (pin "3") (pinfunction "GPIO1_3") (pintype "bidirectional"))
    )
    (net (code "9") (name "/GP2") (class "Default")
      (node (ref "P1") (pin "7") (pinfunction "7_7") (pintype "input"))
      (node (ref "U5") (pin "4") (pinfunction "GPIO2_4") (pintype "bidirectional"))
    )
    (net (code "10") (name "/GP3") (class "Default")
      (node (ref "P1") (pin "9") (pinfunction "9_9") (pintype "input"))
      (node (ref "U5") (pin "5") (pinfunction "GPIO3_5") (pintype "bidirectional"))
    )
    (net (code "11") (name "/GP4") (class "Default")
      (node (ref "P1") (pin "11") (pinfunction "11_11") (pintype "input"))
      (node (ref "U5") (pin "6") (pinfunction "GPIO4_6") (pintype "bidirectional"))
    )
    (net (code "12") (name "/GP5") (class "Default")
      (node (ref "P1") (pin "13") (pinfunction "13_13") (pintype "input"))
      (node (ref "U5") (pin "7") (pinfunction "GPIO5_7") (pintype "bidirectional"))
    )
    (net (code "13") (name "/GP6") (class "Default")
      (node (ref "P1") (pin "17") (pinfunction "17_17") (pintype "input"))
      (node (ref "U5") (pin "8") (pinfunction "GPIO6_8") (pintype "bidirectional"))
    )
    (net (code "14") (name "/GP7") (class "Default")
      (node (ref "P1") (pin "19") (pinfunction "19_19") (pintype "input"))
      (node (ref "U5") (pin "9") (pinfunction "GPIO7_9") (pintype "bidirectional"))
    )
    (net (code "15") (name "/GP8") (class "Default")
      (node (ref "P1") (pin "21") (pinfunction "21_21") (pintype "input"))
      (node (ref "U5") (pin "11") (pinfunction "GPIO8_11") (pintype "bidirectional"))
      (node (ref "U7") (pin "3") (pinfunction "RXD_3") (pintype "input"))
    )
    (net (code "16") (name "/GP9") (class "Default")
      (node (ref "P1") (pin "23") (pinfunction "23_23") (pintype "input"))
      (node (ref "U5") (pin "12") (pinfunction "GPIO9_12") (pintype "bidirectional"))
      (node (ref "U7") (pin "2") (pinfunction "TXD_2") (pintype "input"))
    )
    (net (code "17") (name "/GP10") (class "Default")
      (node (ref "CARD2") (pin "5") (pinfunction "CLX_5") (pintype "input"))
      (node (ref "P1") (pin "27") (pinfunction "27_27") (pintype "input"))
      (node (ref "U5") (pin "13") (pinfunction "GPIO10_13") (pintype "bidirectional"))
    )
    (net (code "18") (name "/GP11") (class "Default")
      (node (ref "CARD2") (pin "3") (pinfunction "CMD_3") (pintype "input"))
      (node (ref "P1") (pin "29") (pinfunction "29_29") (pintype "input"))
      (node (ref "U5") (pin "14") (pinfunction "GPIO11_14") (pintype "bidirectional"))
    )
    (net (code "19") (name "/GP12") (class "Default")
      (node (ref "CARD2") (pin "7") (pinfunction "DAT0_7") (pintype "input"))
      (node (ref "P1") (pin "31") (pinfunction "31_31") (pintype "input"))
      (node (ref "U5") (pin "15") (pinfunction "GPIO12_15") (pintype "bidirectional"))
    )
    (net (code "20") (name "/GP13") (class "Default")
      (node (ref "CARD2") (pin "2") (pinfunction "CD/DAT3_2") (pintype "input"))
      (node (ref "P1") (pin "33") (pinfunction "33_33") (pintype "input"))
      (node (ref "U5") (pin "16") (pinfunction "GPIO13_16") (pintype "bidirectional"))
    )
    (net (code "21") (name "/GP14") (class "Default")
      (node (ref "P1") (pin "37") (pinfunction "37_37") (pintype "input"))
      (node (ref "R11") (pin "1") (pinfunction "1_1") (pintype "input"))
      (node (ref "U14") (pin "7") (pinfunction "SDA_7") (pintype "bidirectional"))
      (node (ref "U5") (pin "17") (pinfunction "GPIO14_17") (pintype "bidirectional"))
    )
    (net (code "22") (name "/GP15") (class "Default")
      (node (ref "P1") (pin "39") (pinfunction "39_39") (pintype "input"))
      (node (ref "R12") (pin "1") (pinfunction "1_1") (pintype "input"))
      (node (ref "U14") (pin "8") (pinfunction "SCL_8") (pintype "unspecified"))
      (node (ref "U5") (pin "18") (pinfunction "GPIO15_18") (pintype "bidirectional"))
    )
    (net (code "23") (name "/GP16") (class "Default")
      (node (ref "L22") (pin "1") (pinfunction "1_1") (pintype "input"))
      (node (ref "P1") (pin "40") (pinfunction "40_40") (pintype "input"))
      (node (ref "U5") (pin "27") (pinfunction "GPIO16_27") (pintype "bidirectional"))
    )
    (net (code "24") (name "/GP17") (class "Default")
      (node (ref "L23") (pin "1") (pinfunction "1_1") (pintype "input"))
      (node (ref "P1") (pin "38") (pinfunction "38_38") (pintype "input"))
      (node (ref "U5") (pin "28") (pinfunction "GPIO17_28") (pintype "bidirectional"))
    )
    (net (code "25") (name "/GP18") (class "Default")
      (node (ref "P1") (pin "34") (pinfunction "34_34") (pintype "input"))
      (node (ref "R13") (pin "1") (pinfunction "1_1") (pintype "input"))
      (node (ref "U5") (pin "29") (pinfunction "GPIO18_29") (pintype "bidirectional"))
    )
    (net (code "26") (name "/GP19") (class "Default")
      (node (ref "P1") (pin "32") (pinfunction "32_32") (pintype "input"))
      (node (ref "R38") (pin "1") (pinfunction "1_1") (pintype "input"))
      (node (ref "U5") (pin "30") (pinfunction "GPIO19_30") (pintype "bidirectional"))
    )
    (net (code "27") (name "/GP20") (class "Default")
      (node (ref "P1") (pin "30") (pinfunction "30_30") (pintype "input"))
      (node (ref "R15") (pin "1") (pinfunction "1_1") (pintype "input"))
      (node (ref "U5") (pin "31") (pinfunction "GPIO20_31") (pintype "bidirectional"))
    )
    (net (code "28") (name "/GP21") (class "Default")
      (node (ref "P1") (pin "28") (pinfunction "28_28") (pintype "input"))
      (node (ref "R14") (pin "1") (pinfunction "1_1") (pintype "input"))
      (node (ref "U5") (pin "32") (pinfunction "GPIO21_32") (pintype "bidirectional"))
    )
    (net (code "29") (name "/GP22") (class "Default")
      (node (ref "P1") (pin "24") (pinfunction "24_24") (pintype "input"))
      (node (ref "U5") (pin "34") (pinfunction "GPIO22_34") (pintype "bidirectional"))
    )
    (net (code "30") (name "/GP23") (class "Default")
      (node (ref "R39") (pin "1") (pinfunction "1_1") (pintype "input"))
      (node (ref "U5") (pin "35") (pinfunction "GPIO23_35") (pintype "bidirectional"))
    )
    (net (code "31") (name "/GP24") (class "Default")
      (node (ref "R40") (pin "1") (pinfunction "1_1") (pintype "input"))
      (node (ref "U5") (pin "36") (pinfunction "GPIO24_36") (pintype "bidirectional"))
    )
    (net (code "32") (name "/GP25") (class "Default")
      (node (ref "R3") (pin "1") (pinfunction "1_1") (pintype "input"))
      (node (ref "U5") (pin "37") (pinfunction "GPIO25_37") (pintype "bidirectional"))
    )
    (net (code "33") (name "/GP26") (class "Default")
      (node (ref "P1") (pin "20") (pinfunction "20_20") (pintype "input"))
      (node (ref "U5") (pin "38") (pinfunction "GPIO26_ADC0_38") (pintype "bidirectional"))
    )
    (net (code "34") (name "/GP27") (class "Default")
      (node (ref "P1") (pin "18") (pinfunction "18_18") (pintype "input"))
      (node (ref "U5") (pin "39") (pinfunction "GPIO27_ADC1_39") (pintype "bidirectional"))
    )
    (net (code "35") (name "/GP28") (class "Default")
      (node (ref "P1") (pin "14") (pinfunction "14_14") (pintype "input"))
      (node (ref "U5") (pin "40") (pinfunction "GPIO28_ADC2_40") (pintype "bidirectional"))
    )
    (net (code "36") (name "/GP29") (class "Default")
      (node (ref "P1") (pin "8") (pinfunction "8_8") (pintype "input"))
      (node (ref "U5") (pin "41") (pinfunction "GPIO29_ADC3_41") (pintype "bidirectional"))
    )
    (net (code "37") (name "/HSYNC") (class "Default")
      (node (ref "DSUB1") (pin "13") (pinfunction "13_13") (pintype "input"))
      (node (ref "R39") (pin "2") (pinfunction "2_2") (pintype "input"))
    )
    (net (code "38") (name "/RUN") (class "Default")
      (node (ref "C19") (pin "2") (pinfunction "2_2") (pintype "input"))
      (node (ref "P1") (pin "22") (pinfunction "22_22") (pintype "input"))
      (node (ref "R28") (pin "1") (pinfunction "1_1") (pintype "input"))
      (node (ref "SW3") (pin "1") (pinfunction "1_1") (pintype "input"))
      (node (ref "U5") (pin "26") (pinfunction "RUN_26") (pintype "input"))
    )
    (net (code "39") (name "/SD-VCC") (class "Default")
      (node (ref "C15") (pin "1") (pinfunction "1_1") (pintype "input"))
      (node (ref "C27") (pin "1") (pinfunction "1_1") (pintype "input"))
      (node (ref "CARD2") (pin "4") (pinfunction "VDD_4") (pintype "input"))
      (node (ref "R29") (pin "2") (pinfunction "2_2") (pintype "input"))
    )
    (net (code "40") (name "/USB-DM") (class "Default")
      (node (ref "U7") (pin "6") (pinfunction "D-_6") (pintype "input"))
      (node (ref "USB2") (pin "A7") (pinfunction "DN1_A7") (pintype "input"))
      (node (ref "USB2") (pin "B7") (pinfunction "DN2_B7") (pintype "input"))
    )
    (net (code "41") (name "/USB-DP") (class "Default")
      (node (ref "U7") (pin "5") (pinfunction "D+_5") (pintype "input"))
      (node (ref "USB2") (pin "A6") (pinfunction "DP1_A6") (pintype "input"))
      (node (ref "USB2") (pin "B6") (pinfunction "DP2_B6") (pintype "input"))
    )
    (net (code "42") (name "/VSYNC") (class "Default")
      (node (ref "DSUB1") (pin "14") (pinfunction "14_14") (pintype "input"))
      (node (ref "R40") (pin "2") (pinfunction "2_2") (pintype "input"))
    )
    (net (code "43") (name "GND") (class "Default")
      (node (ref "BT4") (pin "2") (pinfunction "2_2") (pintype "input"))
      (node (ref "C10") (pin "1") (pinfunction "1_1") (pintype "input"))
      (node (ref "C11") (pin "1") (pinfunction "1_1") (pintype "input"))
      (node (ref "C12") (pin "1") (pinfunction "1_1") (pintype "input"))
      (node (ref "C13") (pin "2") (pinfunction "2_2") (pintype "input"))
      (node (ref "C14") (pin "2") (pinfunction "2_2") (pintype "input"))
      (node (ref "C15") (pin "2") (pinfunction "2_2") (pintype "input"))
      (node (ref "C18") (pin "1") (pinfunction "1_1") (pintype "input"))
      (node (ref "C19") (pin "1") (pinfunction "1_1") (pintype "input"))
      (node (ref "C20") (pin "1") (pinfunction "1_1") (pintype "input"))
      (node (ref "C21") (pin "2") (pinfunction "2_2") (pintype "input"))
      (node (ref "C22") (pin "1") (pinfunction "1_1") (pintype "input"))
      (node (ref "C25") (pin "1") (pinfunction "1_1") (pintype "input"))
      (node (ref "C26") (pin "1") (pinfunction "1_1") (pintype "input"))
      (node (ref "C27") (pin "2") (pinfunction "2_2") (pintype "input"))
      (node (ref "C34") (pin "2") (pinfunction "2_2") (pintype "input"))
      (node (ref "C35") (pin "1") (pinfunction "1_1") (pintype "input"))
      (node (ref "C5") (pin "1") (pinfunction "1_1") (pintype "input"))
      (node (ref "C6") (pin "1") (pinfunction "1_1") (pintype "input"))
      (node (ref "C67") (pin "1") (pinfunction "1_1") (pintype "input"))
      (node (ref "C68") (pin "1") (pinfunction "1_1") (pintype "input"))
      (node (ref "C69") (pin "1") (pinfunction "1_1") (pintype "input"))
      (node (ref "C7") (pin "1") (pinfunction "1_1") (pintype "input"))
      (node (ref "C70") (pin "1") (pinfunction "1_1") (pintype "input"))
      (node (ref "C8") (pin "1") (pinfunction "1_1") (pintype "input"))
      (node (ref "C9") (pin "1") (pinfunction "1_1") (pintype "input"))
      (node (ref "CARD2") (pin "10") (pinfunction "10_10") (pintype "input"))
      (node (ref "CARD2") (pin "11") (pinfunction "11_11") (pintype "input"))
      (node (ref "CARD2") (pin "12") (pinfunction "12_12") (pintype "input"))
      (node (ref "CARD2") (pin "13") (pinfunction "13_13") (pintype "input"))
      (node (ref "CARD2") (pin "6") (pinfunction "VSS_6") (pintype "input"))
      (node (ref "DSUB1") (pin "10") (pinfunction "10_10") (pintype "input"))
      (node (ref "DSUB1") (pin "16") (pinfunction "16_16") (pintype "input"))
      (node (ref "DSUB1") (pin "17") (pinfunction "17_17") (pintype "input"))
      (node (ref "DSUB1") (pin "5") (pinfunction "5_5") (pintype "input"))
      (node (ref "DSUB1") (pin "6") (pinfunction "6_6") (pintype "input"))
      (node (ref "DSUB1") (pin "7") (pinfunction "7_7") (pintype "input"))
      (node (ref "DSUB1") (pin "8") (pinfunction "8_8") (pintype "input"))
      (node (ref "L12") (pin "1") (pinfunction "1_1") (pintype "input"))
      (node (ref "LED1") (pin "1") (pinfunction "-_1") (pintype "input"))
      (node (ref "P1") (pin "15") (pinfunction "15_15") (pintype "input"))
      (node (ref "P1") (pin "16") (pinfunction "16_16") (pintype "input"))
      (node (ref "P1") (pin "25") (pinfunction "25_25") (pintype "input"))
      (node (ref "P1") (pin "26") (pinfunction "26_26") (pintype "input"))
      (node (ref "P1") (pin "35") (pinfunction "35_35") (pintype "input"))
      (node (ref "P1") (pin "36") (pinfunction "36_36") (pintype "input"))
      (node (ref "P1") (pin "5") (pinfunction "5_5") (pintype "input"))
      (node (ref "P1") (pin "6") (pinfunction "6_6") (pintype "input"))
      (node (ref "R31") (pin "1") (pinfunction "1_1") (pintype "input"))
      (node (ref "R32") (pin "1") (pinfunction "1_1") (pintype "input"))
      (node (ref "R33") (pin "1") (pinfunction "1_1") (pintype "input"))
      (node (ref "R46") (pin "2") (pinfunction "2_2") (pintype "input"))
      (node (ref "R47") (pin "2") (pinfunction "2_2") (pintype "input"))
      (node (ref "SW3") (pin "2") (pinfunction "2_2") (pintype "input"))
      (node (ref "SW3") (pin "3") (pinfunction "3_3") (pintype "input"))
      (node (ref "SW3") (pin "4") (pinfunction "4_4") (pintype "input"))
      (node (ref "SW4") (pin "2") (pinfunction "2_2") (pintype "input"))
      (node (ref "SW4") (pin "3") (pinfunction "3_3") (pintype "input"))
      (node (ref "SW4") (pin "4") (pinfunction "4_4") (pintype "input"))
      (node (ref "U1") (pin "1") (pinfunction "GND_1") (pintype "input"))
      (node (ref "U14") (pin "5") (pinfunction "GND_5") (pintype "unspecified"))
      (node (ref "U5") (pin "19") (pinfunction "TESTEN_19") (pintype "input"))
      (node (ref "U5") (pin "57") (pinfunction "GND_57") (pintype "bidirectional"))
      (node (ref "U6") (pin "4") (pinfunction "GND_4") (pintype "input"))
      (node (ref "U7") (pin "1") (pinfunction "GND_1") (pintype "input"))
      (node (ref "USB2") (pin "A1") (pinfunction "GND_A1") (pintype "input"))
      (node (ref "USB2") (pin "A12") (pinfunction "GND_A12") (pintype "input"))
      (node (ref "USB2") (pin "B1") (pinfunction "GND_B1") (pintype "input"))
      (node (ref "USB2") (pin "B12") (pinfunction "GND_B12") (pintype "input"))
      (node (ref "USB5") (pin "4") (pinfunction "GND_4") (pintype "unspecified"))
      (node (ref "USB5") (pin "5") (pinfunction "5_5") (pintype "unspecified"))
      (node (ref "USB5") (pin "6") (pinfunction "6_6") (pintype "unspecified"))
      (node (ref "USB5") (pin "7") (pinfunction "7_7") (pintype "unspecified"))
      (node (ref "X1") (pin "2") (pinfunction "GND_2") (pintype "input"))
      (node (ref "X1") (pin "4") (pinfunction "GND_4") (pintype "input"))
    )
    (net (code "44") (name "Net-(C42-Pad2)") (class "Default")
      (node (ref "C42") (pin "2") (pinfunction "2_2") (pintype "input"))
      (node (ref "L17") (pin "1") (pinfunction "1_1") (pintype "input"))
      (node (ref "U13") (pin "3") (pinfunction "3_3") (pintype "unspecified"))
    )
    (net (code "45") (name "Net-(C43-Pad2)") (class "Default")
      (node (ref "C43") (pin "2") (pinfunction "2_2") (pintype "input"))
      (node (ref "L16") (pin "1") (pinfunction "1_1") (pintype "input"))
      (node (ref "U13") (pin "4") (pinfunction "4_4") (pintype "unspecified"))
    )
    (net (code "46") (name "Net-(C44-Pad2)") (class "Default")
      (node (ref "C44") (pin "2") (pinfunction "2_2") (pintype "input"))
      (node (ref "L19") (pin "1") (pinfunction "1_1") (pintype "input"))
      (node (ref "U13") (pin "1") (pinfunction "1_1") (pintype "unspecified"))
    )
    (net (code "47") (name "Net-(C45-Pad2)") (class "Default")
      (node (ref "C45") (pin "2") (pinfunction "2_2") (pintype "input"))
      (node (ref "L18") (pin "1") (pinfunction "1_1") (pintype "input"))
      (node (ref "U13") (pin "2") (pinfunction "2_2") (pintype "unspecified"))
    )
    (net (code "48") (name "Net-(C48-Pad1)") (class "Default")
      (node (ref "C48") (pin "1") (pinfunction "1_1") (pintype "input"))
      (node (ref "L25") (pin "2") (pinfunction "2_2") (pintype "input"))
    )
    (net (code "49") (name "Net-(C49-Pad1)") (class "Default")
      (node (ref "C49") (pin "1") (pinfunction "1_1") (pintype "input"))
      (node (ref "L26") (pin "2") (pinfunction "2_2") (pintype "input"))
    )
    (net (code "50") (name "Net-(C50-Pad1)") (class "Default")
      (node (ref "C50") (pin "1") (pinfunction "1_1") (pintype "input"))
      (node (ref "L27") (pin "2") (pinfunction "2_2") (pintype "input"))
    )
    (net (code "51") (name "Net-(C51-Pad1)") (class "Default")
      (node (ref "C51") (pin "1") (pinfunction "1_1") (pintype "input"))
      (node (ref "L24") (pin "2") (pinfunction "2_2") (pintype "input"))
    )
    (net (code "52") (name "Net-(C57-Pad2)") (class "Default")
      (node (ref "C57") (pin "2") (pinfunction "2_2") (pintype "input"))
      (node (ref "C62") (pin "1") (pinfunction "1_1") (pintype "input"))
      (node (ref "C64") (pin "1") (pinfunction "1_1") (pintype "input"))
      (node (ref "L1") (pin "1") (pinfunction "1_1") (pintype "input"))
      (node (ref "R34") (pin "2") (pinfunction "2_2") (pintype "input"))
    )
    (net (code "53") (name "Net-(C62-Pad2)") (class "Default")
      (node (ref "C62") (pin "2") (pinfunction "2_2") (pintype "input"))
      (node (ref "C64") (pin "2") (pinfunction "2_2") (pintype "input"))
      (node (ref "C72") (pin "2") (pinfunction "2_2") (pintype "input"))
      (node (ref "C74") (pin "2") (pinfunction "2_2") (pintype "input"))
      (node (ref "CN3") (pin "2") (pinfunction "2_2") (pintype "input"))
      (node (ref "L1") (pin "2") (pinfunction "2_2") (pintype "input"))
      (node (ref "R42") (pin "1") (pinfunction "1_1") (pintype "input"))
    )
    (net (code "54") (name "Net-(C71-Pad2)") (class "Default")
      (node (ref "C71") (pin "2") (pinfunction "2_2") (pintype "input"))
      (node (ref "C76") (pin "1") (pinfunction "1_1") (pintype "input"))
      (node (ref "C77") (pin "1") (pinfunction "1_1") (pintype "input"))
      (node (ref "L2") (pin "1") (pinfunction "1_1") (pintype "input"))
      (node (ref "R35") (pin "2") (pinfunction "2_2") (pintype "input"))
    )
    (net (code "55") (name "Net-(C73-Pad2)") (class "Default")
      (node (ref "C73") (pin "2") (pinfunction "2_2") (pintype "input"))
      (node (ref "C75") (pin "2") (pinfunction "2_2") (pintype "input"))
      (node (ref "C76") (pin "2") (pinfunction "2_2") (pintype "input"))
      (node (ref "C77") (pin "2") (pinfunction "2_2") (pintype "input"))
      (node (ref "CN3") (pin "3") (pinfunction "3_3") (pintype "input"))
      (node (ref "L2") (pin "2") (pinfunction "2_2") (pintype "input"))
      (node (ref "R43") (pin "1") (pinfunction "1_1") (pintype "input"))
    )
    (net (code "56") (name "Net-(DSUB1-Pad1)") (class "Default")
      (node (ref "DSUB1") (pin "1") (pinfunction "1_1") (pintype "input"))
      (node (ref "R14") (pin "2") (pinfunction "2_2") (pintype "input"))
    )
    (net (code "57") (name "Net-(DSUB1-Pad2)") (class "Default")
      (node (ref "DSUB1") (pin "2") (pinfunction "2_2") (pintype "input"))
      (node (ref "R15") (pin "2") (pinfunction "2_2") (pintype "input"))
      (node (ref "R38") (pin "2") (pinfunction "2_2") (pintype "input"))
    )
    (net (code "58") (name "Net-(DSUB1-Pad3)") (class "Default")
      (node (ref "DSUB1") (pin "3") (pinfunction "3_3") (pintype "input"))
      (node (ref "R13") (pin "2") (pinfunction "2_2") (pintype "input"))
    )
    (net (code "59") (name "Net-(L22-Pad2)") (class "Default")
      (node (ref "L22") (pin "2") (pinfunction "2_2") (pintype "input"))
      (node (ref "R34") (pin "1") (pinfunction "1_1") (pintype "input"))
    )
    (net (code "60") (name "Net-(L23-Pad2)") (class "Default")
      (node (ref "L23") (pin "2") (pinfunction "2_2") (pintype "input"))
      (node (ref "R35") (pin "1") (pinfunction "1_1") (pintype "input"))
    )
    (net (code "61") (name "Net-(L26-Pad1)") (class "Default")
      (node (ref "L26") (pin "1") (pinfunction "1_1") (pintype "input"))
      (node (ref "VR1") (pin "2") (pinfunction "2_2") (pintype "input"))
    )
    (net (code "62") (name "Net-(L27-Pad1)") (class "Default")
      (node (ref "L27") (pin "1") (pinfunction "1_1") (pintype "input"))
      (node (ref "VR1") (pin "4") (pinfunction "4_4") (pintype "input"))
    )
    (net (code "63") (name "Net-(LED1-+)") (class "Default")
      (node (ref "LED1") (pin "2") (pinfunction "+_2") (pintype "input"))
      (node (ref "R3") (pin "2") (pinfunction "2_2") (pintype "input"))
    )
    (net (code "64") (name "Net-(R4-Pad2)") (class "Default")
      (node (ref "R4") (pin "2") (pinfunction "2_2") (pintype "input"))
      (node (ref "SW4") (pin "1") (pinfunction "1_1") (pintype "input"))
    )
    (net (code "65") (name "Net-(R33-Pad2)") (class "Default")
      (node (ref "R33") (pin "2") (pinfunction "2_2") (pintype "input"))
      (node (ref "USB2") (pin "1") (pinfunction "EP_1") (pintype "input"))
      (node (ref "USB2") (pin "2") (pinfunction "EP_2") (pintype "input"))
      (node (ref "USB2") (pin "3") (pinfunction "EP_3") (pintype "input"))
      (node (ref "USB2") (pin "4") (pinfunction "EP_4") (pintype "input"))
    )
    (net (code "66") (name "Net-(R42-Pad2)") (class "Default")
      (node (ref "R42") (pin "2") (pinfunction "2_2") (pintype "input"))
      (node (ref "VR1") (pin "5") (pinfunction "5_5") (pintype "input"))
    )
    (net (code "67") (name "Net-(R43-Pad2)") (class "Default")
      (node (ref "R43") (pin "2") (pinfunction "2_2") (pintype "input"))
      (node (ref "VR1") (pin "3") (pinfunction "3_3") (pintype "input"))
    )
    (net (code "68") (name "Net-(U5-QSPI_SCLK)") (class "Default")
      (node (ref "U5") (pin "52") (pinfunction "QSPI_SCLK_52") (pintype "output"))
      (node (ref "U6") (pin "6") (pinfunction "CLK_6") (pintype "input"))
    )
    (net (code "69") (name "Net-(U5-QSPI_SD0)") (class "Default")
      (node (ref "U5") (pin "53") (pinfunction "QSPI_SD0_53") (pintype "bidirectional"))
      (node (ref "U6") (pin "5") (pinfunction "DI_5") (pintype "input"))
    )
    (net (code "70") (name "Net-(U5-QSPI_SD1)") (class "Default")
      (node (ref "U5") (pin "55") (pinfunction "QSPI_SD1_55") (pintype "bidirectional"))
      (node (ref "U6") (pin "2") (pinfunction "DO_2") (pintype "input"))
    )
    (net (code "71") (name "Net-(U5-QSPI_SD2)") (class "Default")
      (node (ref "U5") (pin "54") (pinfunction "QSPI_SD2_54") (pintype "bidirectional"))
      (node (ref "U6") (pin "3") (pinfunction "IO2_3") (pintype "input"))
    )
    (net (code "72") (name "Net-(U5-QSPI_SD3)") (class "Default")
      (node (ref "U5") (pin "51") (pinfunction "QSPI_SD3_51") (pintype "bidirectional"))
      (node (ref "U6") (pin "7") (pinfunction "IO3_7") (pintype "input"))
    )
    (net (code "73") (name "Net-(U5-QSPI_SS)") (class "Default")
      (node (ref "R23") (pin "1") (pinfunction "1_1") (pintype "input"))
      (node (ref "R4") (pin "1") (pinfunction "1_1") (pintype "input"))
      (node (ref "U5") (pin "56") (pinfunction "QSPI_SS_56") (pintype "bidirectional"))
      (node (ref "U6") (pin "1") (pinfunction "CS#_1") (pintype "input"))
    )
    (net (code "74") (name "Net-(U5-USB_DM)") (class "Default")
      (node (ref "R59") (pin "1") (pinfunction "1_1") (pintype "input"))
      (node (ref "R60") (pin "1") (pinfunction "1_1") (pintype "input"))
      (node (ref "U5") (pin "46") (pinfunction "USB_DM_46") (pintype "bidirectional"))
    )
    (net (code "75") (name "Net-(U5-USB_DP)") (class "Default")
      (node (ref "R57") (pin "1") (pinfunction "1_1") (pintype "input"))
      (node (ref "R58") (pin "1") (pinfunction "1_1") (pintype "input"))
      (node (ref "U5") (pin "47") (pinfunction "USB_DP_47") (pintype "bidirectional"))
    )
    (net (code "76") (name "Net-(U5-XIN)") (class "Default")
      (node (ref "C67") (pin "2") (pinfunction "2_2") (pintype "input"))
      (node (ref "C69") (pin "2") (pinfunction "2_2") (pintype "input"))
      (node (ref "U5") (pin "20") (pinfunction "XIN_20") (pintype "input"))
      (node (ref "X1") (pin "3") (pinfunction "OSC2_3") (pintype "input"))
    )
    (net (code "77") (name "Net-(U5-XOUT)") (class "Default")
      (node (ref "R5") (pin "2") (pinfunction "2_2") (pintype "input"))
      (node (ref "U5") (pin "21") (pinfunction "XOUT_21") (pintype "input"))
    )
    (net (code "78") (name "Net-(U8-IN+)") (class "Default")
      (node (ref "C49") (pin "2") (pinfunction "2_2") (pintype "input"))
      (node (ref "U8") (pin "3") (pinfunction "IN+_3") (pintype "input"))
    )
    (net (code "79") (name "Net-(U8-IN-)") (class "Default")
      (node (ref "C48") (pin "2") (pinfunction "2_2") (pintype "input"))
      (node (ref "U8") (pin "4") (pinfunction "IN-_4") (pintype "input"))
    )
    (net (code "80") (name "Net-(U8-SD#)") (class "Default")
      (node (ref "R45") (pin "1") (pinfunction "1_1") (pintype "input"))
      (node (ref "U8") (pin "1") (pinfunction "SD#_1") (pintype "input"))
    )
    (net (code "81") (name "Net-(U8-VO+)") (class "Default")
      (node (ref "L18") (pin "2") (pinfunction "2_2") (pintype "input"))
      (node (ref "U8") (pin "5") (pinfunction "VO+_5") (pintype "output"))
    )
    (net (code "82") (name "Net-(U8-VO-)") (class "Default")
      (node (ref "L19") (pin "2") (pinfunction "2_2") (pintype "input"))
      (node (ref "U8") (pin "8") (pinfunction "VO-_8") (pintype "input"))
    )
    (net (code "83") (name "Net-(U9-IN+)") (class "Default")
      (node (ref "C50") (pin "2") (pinfunction "2_2") (pintype "input"))
      (node (ref "U9") (pin "3") (pinfunction "IN+_3") (pintype "input"))
    )
    (net (code "84") (name "Net-(U9-IN-)") (class "Default")
      (node (ref "C51") (pin "2") (pinfunction "2_2") (pintype "input"))
      (node (ref "U9") (pin "4") (pinfunction "IN-_4") (pintype "input"))
    )
    (net (code "85") (name "Net-(U9-SD#)") (class "Default")
      (node (ref "R44") (pin "1") (pinfunction "1_1") (pintype "input"))
      (node (ref "U9") (pin "1") (pinfunction "SD#_1") (pintype "input"))
    )
    (net (code "86") (name "Net-(U9-VO+)") (class "Default")
      (node (ref "L16") (pin "2") (pinfunction "2_2") (pintype "input"))
      (node (ref "U9") (pin "5") (pinfunction "VO+_5") (pintype "output"))
    )
    (net (code "87") (name "Net-(U9-VO-)") (class "Default")
      (node (ref "L17") (pin "2") (pinfunction "2_2") (pintype "input"))
      (node (ref "U9") (pin "8") (pinfunction "VO-_8") (pintype "input"))
    )
    (net (code "88") (name "Net-(U14-VBAT)") (class "Default")
      (node (ref "BT4") (pin "1") (pinfunction "1_1") (pintype "input"))
      (node (ref "U14") (pin "6") (pinfunction "VBAT_6") (pintype "unspecified"))
    )
    (net (code "89") (name "Net-(USB2-CC1)") (class "Default")
      (node (ref "R32") (pin "2") (pinfunction "2_2") (pintype "input"))
      (node (ref "USB2") (pin "A5") (pinfunction "CC1_A5") (pintype "input"))
    )
    (net (code "90") (name "Net-(USB2-CC2)") (class "Default")
      (node (ref "R31") (pin "2") (pinfunction "2_2") (pintype "input"))
      (node (ref "USB2") (pin "B5") (pinfunction "CC2_B5") (pintype "input"))
    )
    (net (code "91") (name "Net-(USB5-D+)") (class "Default")
      (node (ref "R47") (pin "1") (pinfunction "1_1") (pintype "input"))
      (node (ref "R57") (pin "2") (pinfunction "2_2") (pintype "input"))
      (node (ref "R58") (pin "2") (pinfunction "2_2") (pintype "input"))
      (node (ref "USB5") (pin "3") (pinfunction "D+_3") (pintype "unspecified"))
    )
    (net (code "92") (name "Net-(USB5-D-)") (class "Default")
      (node (ref "R46") (pin "1") (pinfunction "1_1") (pintype "input"))
      (node (ref "R59") (pin "2") (pinfunction "2_2") (pintype "input"))
      (node (ref "R60") (pin "2") (pinfunction "2_2") (pintype "input"))
      (node (ref "USB5") (pin "2") (pinfunction "D-_2") (pintype "unspecified"))
    )
    (net (code "93") (name "Net-(X1-OSC1)") (class "Default")
      (node (ref "C68") (pin "2") (pinfunction "2_2") (pintype "input"))
      (node (ref "C70") (pin "2") (pinfunction "2_2") (pintype "input"))
      (node (ref "R5") (pin "1") (pinfunction "1_1") (pintype "input"))
      (node (ref "X1") (pin "1") (pinfunction "OSC1_1") (pintype "input"))
    )
    (net (code "94") (name "VCC") (class "Default")
      (node (ref "C10") (pin "2") (pinfunction "2_2") (pintype "input"))
      (node (ref "C11") (pin "2") (pinfunction "2_2") (pintype "input"))
      (node (ref "C12") (pin "2") (pinfunction "2_2") (pintype "input"))
      (node (ref "C18") (pin "2") (pinfunction "2_2") (pintype "input"))
      (node (ref "C20") (pin "2") (pinfunction "2_2") (pintype "input"))
      (node (ref "C22") (pin "2") (pinfunction "2_2") (pintype "input"))
      (node (ref "C26") (pin "2") (pinfunction "2_2") (pintype "input"))
      (node (ref "C34") (pin "1") (pinfunction "1_1") (pintype "input"))
      (node (ref "C5") (pin "2") (pinfunction "2_2") (pintype "input"))
      (node (ref "C6") (pin "2") (pinfunction "2_2") (pintype "input"))
      (node (ref "C7") (pin "2") (pinfunction "2_2") (pintype "input"))
      (node (ref "C8") (pin "2") (pinfunction "2_2") (pintype "input"))
      (node (ref "C9") (pin "2") (pinfunction "2_2") (pintype "input"))
      (node (ref "L28") (pin "2") (pinfunction "2_2") (pintype "input"))
      (node (ref "P1") (pin "10") (pinfunction "10_10") (pintype "input"))
      (node (ref "P1") (pin "12") (pinfunction "12_12") (pintype "input"))
      (node (ref "R11") (pin "2") (pinfunction "2_2") (pintype "input"))
      (node (ref "R12") (pin "2") (pinfunction "2_2") (pintype "input"))
      (node (ref "R23") (pin "2") (pinfunction "2_2") (pintype "input"))
      (node (ref "R28") (pin "2") (pinfunction "2_2") (pintype "input"))
      (node (ref "R29") (pin "1") (pinfunction "1_1") (pintype "input"))
      (node (ref "U1") (pin "2") (pinfunction "VOUT_2") (pintype "input"))
      (node (ref "U1") (pin "4") (pinfunction "VOUT_4") (pintype "input"))
      (node (ref "U14") (pin "2") (pinfunction "VCC_2") (pintype "unspecified"))
      (node (ref "U14") (pin "4") (pinfunction "RST#_4") (pintype "bidirectional"))
      (node (ref "U5") (pin "1") (pinfunction "IOVDD_1") (pintype "bidirectional"))
      (node (ref "U5") (pin "10") (pinfunction "IOVDD_10") (pintype "bidirectional"))
      (node (ref "U5") (pin "22") (pinfunction "IOVDD_22") (pintype "bidirectional"))
      (node (ref "U5") (pin "33") (pinfunction "IOVDD_33") (pintype "bidirectional"))
      (node (ref "U5") (pin "42") (pinfunction "IOVDD_42") (pintype "bidirectional"))
      (node (ref "U5") (pin "44") (pinfunction "VREG_IN_44") (pintype "bidirectional"))
      (node (ref "U5") (pin "48") (pinfunction "USB_VDD_48") (pintype "bidirectional"))
      (node (ref "U5") (pin "49") (pinfunction "IOVDD_49") (pintype "bidirectional"))
      (node (ref "U6") (pin "8") (pinfunction "VCC_8") (pintype "input"))
      (node (ref "U7") (pin "16") (pinfunction "VCC_16") (pintype "input"))
      (node (ref "U7") (pin "4") (pinfunction "V3_4") (pintype "input"))
    )
    (net (code "95") (name "unconnected-(CARD2-DAT1-Pad8)") (class "Default")
      (node (ref "CARD2") (pin "8") (pinfunction "DAT1_8") (pintype "input+no_connect"))
    )
    (net (code "96") (name "unconnected-(CARD2-DAT2-Pad1)") (class "Default")
      (node (ref "CARD2") (pin "1") (pinfunction "DAT2_1") (pintype "input+no_connect"))
    )
    (net (code "97") (name "unconnected-(CARD2-PadCD)") (class "Default")
      (node (ref "CARD2") (pin "CD") (pinfunction "CD_CD") (pintype "input+no_connect"))
    )
    (net (code "98") (name "unconnected-(DSUB1-Pad4)") (class "Default")
      (node (ref "DSUB1") (pin "4") (pinfunction "4_4") (pintype "input+no_connect"))
    )
    (net (code "99") (name "unconnected-(DSUB1-Pad9)") (class "Default")
      (node (ref "DSUB1") (pin "9") (pinfunction "9_9") (pintype "input+no_connect"))
    )
    (net (code "100") (name "unconnected-(DSUB1-Pad11)") (class "Default")
      (node (ref "DSUB1") (pin "11") (pinfunction "11_11") (pintype "input+no_connect"))
    )
    (net (code "101") (name "unconnected-(DSUB1-Pad12)") (class "Default")
      (node (ref "DSUB1") (pin "12") (pinfunction "12_12") (pintype "input+no_connect"))
    )
    (net (code "102") (name "unconnected-(DSUB1-Pad15)") (class "Default")
      (node (ref "DSUB1") (pin "15") (pinfunction "15_15") (pintype "input+no_connect"))
    )
    (net (code "103") (name "unconnected-(U5-SWCLK-Pad24)") (class "Default")
      (node (ref "U5") (pin "24") (pinfunction "SWCLK_24") (pintype "output+no_connect"))
    )
    (net (code "104") (name "unconnected-(U5-SWD-Pad25)") (class "Default")
      (node (ref "U5") (pin "25") (pinfunction "SWD_25") (pintype "bidirectional+no_connect"))
    )
    (net (code "105") (name "unconnected-(U7-CTS#-Pad9)") (class "Default")
      (node (ref "U7") (pin "9") (pinfunction "CTS#_9") (pintype "input+no_connect"))
    )
    (net (code "106") (name "unconnected-(U7-DCD#-Pad12)") (class "Default")
      (node (ref "U7") (pin "12") (pinfunction "DCD#_12") (pintype "input+no_connect"))
    )
    (net (code "107") (name "unconnected-(U7-DSR#-Pad10)") (class "Default")
      (node (ref "U7") (pin "10") (pinfunction "DSR#_10") (pintype "input+no_connect"))
    )
    (net (code "108") (name "unconnected-(U7-DTR#-Pad13)") (class "Default")
      (node (ref "U7") (pin "13") (pinfunction "DTR#_13") (pintype "input+no_connect"))
    )
    (net (code "109") (name "unconnected-(U7-NC.-Pad7)") (class "Default")
      (node (ref "U7") (pin "7") (pinfunction "NC._7") (pintype "input+no_connect"))
    )
    (net (code "110") (name "unconnected-(U7-OUT#-Pad8)") (class "Default")
      (node (ref "U7") (pin "8") (pinfunction "OUT#_8") (pintype "input+no_connect"))
    )
    (net (code "111") (name "unconnected-(U7-R232-Pad15)") (class "Default")
      (node (ref "U7") (pin "15") (pinfunction "R232_15") (pintype "input+no_connect"))
    )
    (net (code "112") (name "unconnected-(U7-RI#-Pad11)") (class "Default")
      (node (ref "U7") (pin "11") (pinfunction "RI#_11") (pintype "input+no_connect"))
    )
    (net (code "113") (name "unconnected-(U7-RTS#-Pad14)") (class "Default")
      (node (ref "U7") (pin "14") (pinfunction "RTS#_14") (pintype "input+no_connect"))
    )
    (net (code "114") (name "unconnected-(U8-NC-Pad2)") (class "Default")
      (node (ref "U8") (pin "2") (pinfunction "NC_2") (pintype "input+no_connect"))
    )
    (net (code "115") (name "unconnected-(U9-NC-Pad2)") (class "Default")
      (node (ref "U9") (pin "2") (pinfunction "NC_2") (pintype "input+no_connect"))
    )
    (net (code "116") (name "unconnected-(U14-32kHz-Pad1)") (class "Default")
      (node (ref "U14") (pin "1") (pinfunction "32kHz_1") (pintype "unspecified+no_connect"))
    )
    (net (code "117") (name "unconnected-(U14-INT#{slash}SQW-Pad3)") (class "Default")
      (node (ref "U14") (pin "3") (pinfunction "INT#/SQW_3") (pintype "bidirectional+no_connect"))
    )
    (net (code "118") (name "unconnected-(USB2-SUB1-PadA8)") (class "Default")
      (node (ref "USB2") (pin "A8") (pinfunction "SUB1_A8") (pintype "input+no_connect"))
    )
    (net (code "119") (name "unconnected-(USB2-SUB2-PadB8)") (class "Default")
      (node (ref "USB2") (pin "B8") (pinfunction "SUB2_B8") (pintype "input+no_connect"))
    )
  )
)
